# HolderDog.net
KiCad netlist of a schematic drawn in Altium Designer
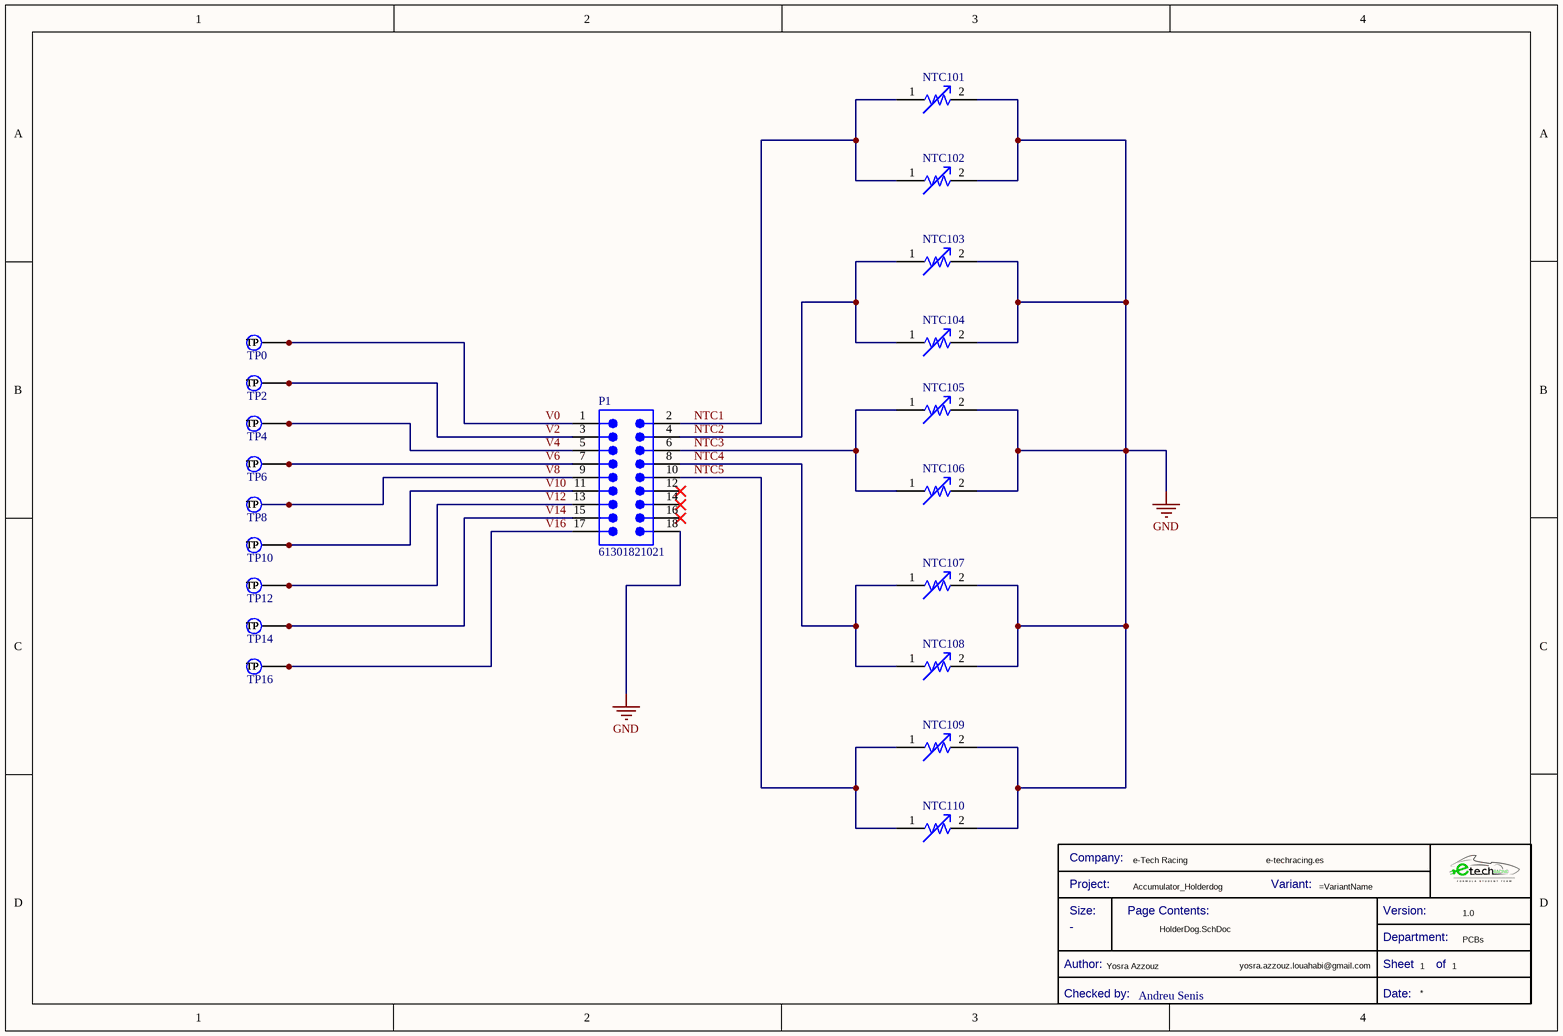
[diagram p0: HolderDog.SchDoc]

(export (version "E")
  (design (tool "Eeschema 10.0.6"))
  (components
    (comp (ref "*")
      (value "Title Block_template")
      (description "Standard Title Block")
      (fields
        (field (name "SIZE") "-")
        (field (name ".CREATOR") "GP")
        (field (name ".PCBCHECK") "GP")
        (field (name ".SCHCHECK") "GP")
      )
      (libsource (lib "e-Tech_Racing") (part "Title Block_template"))
    )
    (comp (ref "NTC101")
      (value "NTC SMD 0805")
      (footprint "RESC2012X10N")
      (description "NTC 0805 package 10kR")
      (libsource (lib "EMEA- E-Tech Racing- I'Escola d'Enginyeria de Barcelona Est") (part "0805"))
    )
    (comp (ref "NTC102")
      (value "NTC SMD 0805")
      (footprint "RESC2012X10N")
      (description "NTC 0805 package 10kR")
      (libsource (lib "EMEA- E-Tech Racing- I'Escola d'Enginyeria de Barcelona Est") (part "0805"))
    )
    (comp (ref "NTC103")
      (value "NTC SMD 0805")
      (footprint "RESC2012X10N")
      (description "NTC 0805 package 10kR")
      (libsource (lib "EMEA- E-Tech Racing- I'Escola d'Enginyeria de Barcelona Est") (part "0805"))
    )
    (comp (ref "NTC104")
      (value "NTC SMD 0805")
      (footprint "RESC2012X10N")
      (description "NTC 0805 package 10kR")
      (libsource (lib "EMEA- E-Tech Racing- I'Escola d'Enginyeria de Barcelona Est") (part "0805"))
    )
    (comp (ref "NTC105")
      (value "NTC SMD 0805")
      (footprint "RESC2012X10N")
      (description "NTC 0805 package 10kR")
      (libsource (lib "EMEA- E-Tech Racing- I'Escola d'Enginyeria de Barcelona Est") (part "0805"))
    )
    (comp (ref "NTC106")
      (value "NTC SMD 0805")
      (footprint "RESC2012X10N")
      (description "NTC 0805 package 10kR")
      (libsource (lib "EMEA- E-Tech Racing- I'Escola d'Enginyeria de Barcelona Est") (part "0805"))
    )
    (comp (ref "NTC107")
      (value "NTC SMD 0805")
      (footprint "RESC2012X10N")
      (description "NTC 0805 package 10kR")
      (libsource (lib "EMEA- E-Tech Racing- I'Escola d'Enginyeria de Barcelona Est") (part "0805"))
    )
    (comp (ref "NTC108")
      (value "NTC SMD 0805")
      (footprint "RESC2012X10N")
      (description "NTC 0805 package 10kR")
      (libsource (lib "EMEA- E-Tech Racing- I'Escola d'Enginyeria de Barcelona Est") (part "0805"))
    )
    (comp (ref "NTC109")
      (value "NTC SMD 0805")
      (footprint "RESC2012X10N")
      (description "NTC 0805 package 10kR")
      (libsource (lib "EMEA- E-Tech Racing- I'Escola d'Enginyeria de Barcelona Est") (part "0805"))
    )
    (comp (ref "NTC110")
      (value "NTC SMD 0805")
      (footprint "RESC2012X10N")
      (description "NTC 0805 package 10kR")
      (libsource (lib "EMEA- E-Tech Racing- I'Escola d'Enginyeria de Barcelona Est") (part "0805"))
    )
    (comp (ref "P1")
      (value "61301821021")
      (footprint "61301821021")
      (libsource (lib "EMEA- E-Tech Racing- I'Escola d'Enginyeria de Barcelona Est") (part "Header_Male_2R_18P"))
    )
    (comp (ref "TP0")
      (value "Test Point")
      (footprint "TESTPOINT_WIDE")
      (description "TestPoint 5x5mm")
      (libsource (lib "e-Tech_Racing") (part "TestPoint_Wide"))
    )
    (comp (ref "TP2")
      (value "Test Point")
      (footprint "TESTPOINT_WIDE")
      (description "TestPoint 5x5mm")
      (libsource (lib "e-Tech_Racing") (part "TestPoint_Wide"))
    )
    (comp (ref "TP4")
      (value "Test Point")
      (footprint "TESTPOINT_WIDE")
      (description "TestPoint 5x5mm")
      (libsource (lib "e-Tech_Racing") (part "TestPoint_Wide"))
    )
    (comp (ref "TP6")
      (value "Test Point")
      (footprint "TESTPOINT_WIDE")
      (description "TestPoint 5x5mm")
      (libsource (lib "e-Tech_Racing") (part "TestPoint_Wide"))
    )
    (comp (ref "TP8")
      (value "Test Point")
      (footprint "TESTPOINT_WIDE")
      (description "TestPoint 5x5mm")
      (libsource (lib "e-Tech_Racing") (part "TestPoint_Wide"))
    )
    (comp (ref "TP10")
      (value "Test Point")
      (footprint "TESTPOINT_WIDE")
      (description "TestPoint 5x5mm")
      (libsource (lib "e-Tech_Racing") (part "TestPoint_Wide"))
    )
    (comp (ref "TP12")
      (value "Test Point")
      (footprint "TESTPOINT_WIDE")
      (description "TestPoint 5x5mm")
      (libsource (lib "e-Tech_Racing") (part "TestPoint_Wide"))
    )
    (comp (ref "TP14")
      (value "Test Point")
      (footprint "TESTPOINT_WIDE")
      (description "TestPoint 5x5mm")
      (libsource (lib "e-Tech_Racing") (part "TestPoint_Wide"))
    )
    (comp (ref "TP16")
      (value "Test Point")
      (footprint "TESTPOINT_WIDE")
      (description "TestPoint 5x5mm")
      (libsource (lib "e-Tech_Racing") (part "TestPoint_Wide"))
    )
  )
  (nets
    (net (code "1") (name "/NTC1") (class "Default")
      (node (ref "NTC101") (pin "1") (pinfunction "1_1") (pintype "passive"))
      (node (ref "NTC102") (pin "1") (pinfunction "1_1") (pintype "passive"))
      (node (ref "P1") (pin "2") (pinfunction "2_2") (pintype "passive"))
    )
    (net (code "2") (name "/NTC2") (class "Default")
      (node (ref "NTC103") (pin "1") (pinfunction "1_1") (pintype "passive"))
      (node (ref "NTC104") (pin "1") (pinfunction "1_1") (pintype "passive"))
      (node (ref "P1") (pin "4") (pinfunction "4_4") (pintype "passive"))
    )
    (net (code "3") (name "/NTC3") (class "Default")
      (node (ref "NTC105") (pin "1") (pinfunction "1_1") (pintype "passive"))
      (node (ref "NTC106") (pin "1") (pinfunction "1_1") (pintype "passive"))
      (node (ref "P1") (pin "6") (pinfunction "6_6") (pintype "passive"))
    )
    (net (code "4") (name "/NTC4") (class "Default")
      (node (ref "NTC107") (pin "1") (pinfunction "1_1") (pintype "passive"))
      (node (ref "NTC108") (pin "1") (pinfunction "1_1") (pintype "passive"))
      (node (ref "P1") (pin "8") (pinfunction "8_8") (pintype "passive"))
    )
    (net (code "5") (name "/NTC5") (class "Default")
      (node (ref "NTC109") (pin "1") (pinfunction "1_1") (pintype "passive"))
      (node (ref "NTC110") (pin "1") (pinfunction "1_1") (pintype "passive"))
      (node (ref "P1") (pin "10") (pinfunction "10_10") (pintype "passive"))
    )
    (net (code "6") (name "/V0") (class "Default")
      (node (ref "P1") (pin "1") (pinfunction "1_1") (pintype "passive"))
      (node (ref "TP0") (pin "1") (pinfunction "TP_1") (pintype "passive"))
    )
    (net (code "7") (name "/V2") (class "Default")
      (node (ref "P1") (pin "3") (pinfunction "3_3") (pintype "passive"))
      (node (ref "TP2") (pin "1") (pinfunction "TP_1") (pintype "passive"))
    )
    (net (code "8") (name "/V4") (class "Default")
      (node (ref "P1") (pin "5") (pinfunction "5_5") (pintype "passive"))
      (node (ref "TP4") (pin "1") (pinfunction "TP_1") (pintype "passive"))
    )
    (net (code "9") (name "/V6") (class "Default")
      (node (ref "P1") (pin "7") (pinfunction "7_7") (pintype "passive"))
      (node (ref "TP6") (pin "1") (pinfunction "TP_1") (pintype "passive"))
    )
    (net (code "10") (name "/V8") (class "Default")
      (node (ref "P1") (pin "9") (pinfunction "9_9") (pintype "passive"))
      (node (ref "TP8") (pin "1") (pinfunction "TP_1") (pintype "passive"))
    )
    (net (code "11") (name "/V10") (class "Default")
      (node (ref "P1") (pin "11") (pinfunction "11_11") (pintype "passive"))
      (node (ref "TP10") (pin "1") (pinfunction "TP_1") (pintype "passive"))
    )
    (net (code "12") (name "/V12") (class "Default")
      (node (ref "P1") (pin "13") (pinfunction "13_13") (pintype "passive"))
      (node (ref "TP12") (pin "1") (pinfunction "TP_1") (pintype "passive"))
    )
    (net (code "13") (name "/V14") (class "Default")
      (node (ref "P1") (pin "15") (pinfunction "15_15") (pintype "passive"))
      (node (ref "TP14") (pin "1") (pinfunction "TP_1") (pintype "passive"))
    )
    (net (code "14") (name "/V16") (class "Default")
      (node (ref "P1") (pin "17") (pinfunction "17_17") (pintype "passive"))
      (node (ref "TP16") (pin "1") (pinfunction "TP_1") (pintype "passive"))
    )
    (net (code "15") (name "GND") (class "Default")
      (node (ref "NTC101") (pin "2") (pinfunction "2_2") (pintype "passive"))
      (node (ref "NTC102") (pin "2") (pinfunction "2_2") (pintype "passive"))
      (node (ref "NTC103") (pin "2") (pinfunction "2_2") (pintype "passive"))
      (node (ref "NTC104") (pin "2") (pinfunction "2_2") (pintype "passive"))
      (node (ref "NTC105") (pin "2") (pinfunction "2_2") (pintype "passive"))
      (node (ref "NTC106") (pin "2") (pinfunction "2_2") (pintype "passive"))
      (node (ref "NTC107") (pin "2") (pinfunction "2_2") (pintype "passive"))
      (node (ref "NTC108") (pin "2") (pinfunction "2_2") (pintype "passive"))
      (node (ref "NTC109") (pin "2") (pinfunction "2_2") (pintype "passive"))
      (node (ref "NTC110") (pin "2") (pinfunction "2_2") (pintype "passive"))
      (node (ref "P1") (pin "18") (pinfunction "18_18") (pintype "passive"))
    )
    (net (code "16") (name "unconnected-(P1-Pad12)") (class "Default")
      (node (ref "P1") (pin "12") (pinfunction "12_12") (pintype "passive+no_connect"))
    )
    (net (code "17") (name "unconnected-(P1-Pad14)") (class "Default")
      (node (ref "P1") (pin "14") (pinfunction "14_14") (pintype "passive+no_connect"))
    )
    (net (code "18") (name "unconnected-(P1-Pad16)") (class "Default")
      (node (ref "P1") (pin "16") (pinfunction "16_16") (pintype "passive+no_connect"))
    )
  )
)
